# Power_Schematic.net
KiCad netlist of a schematic drawn in Altium Designer
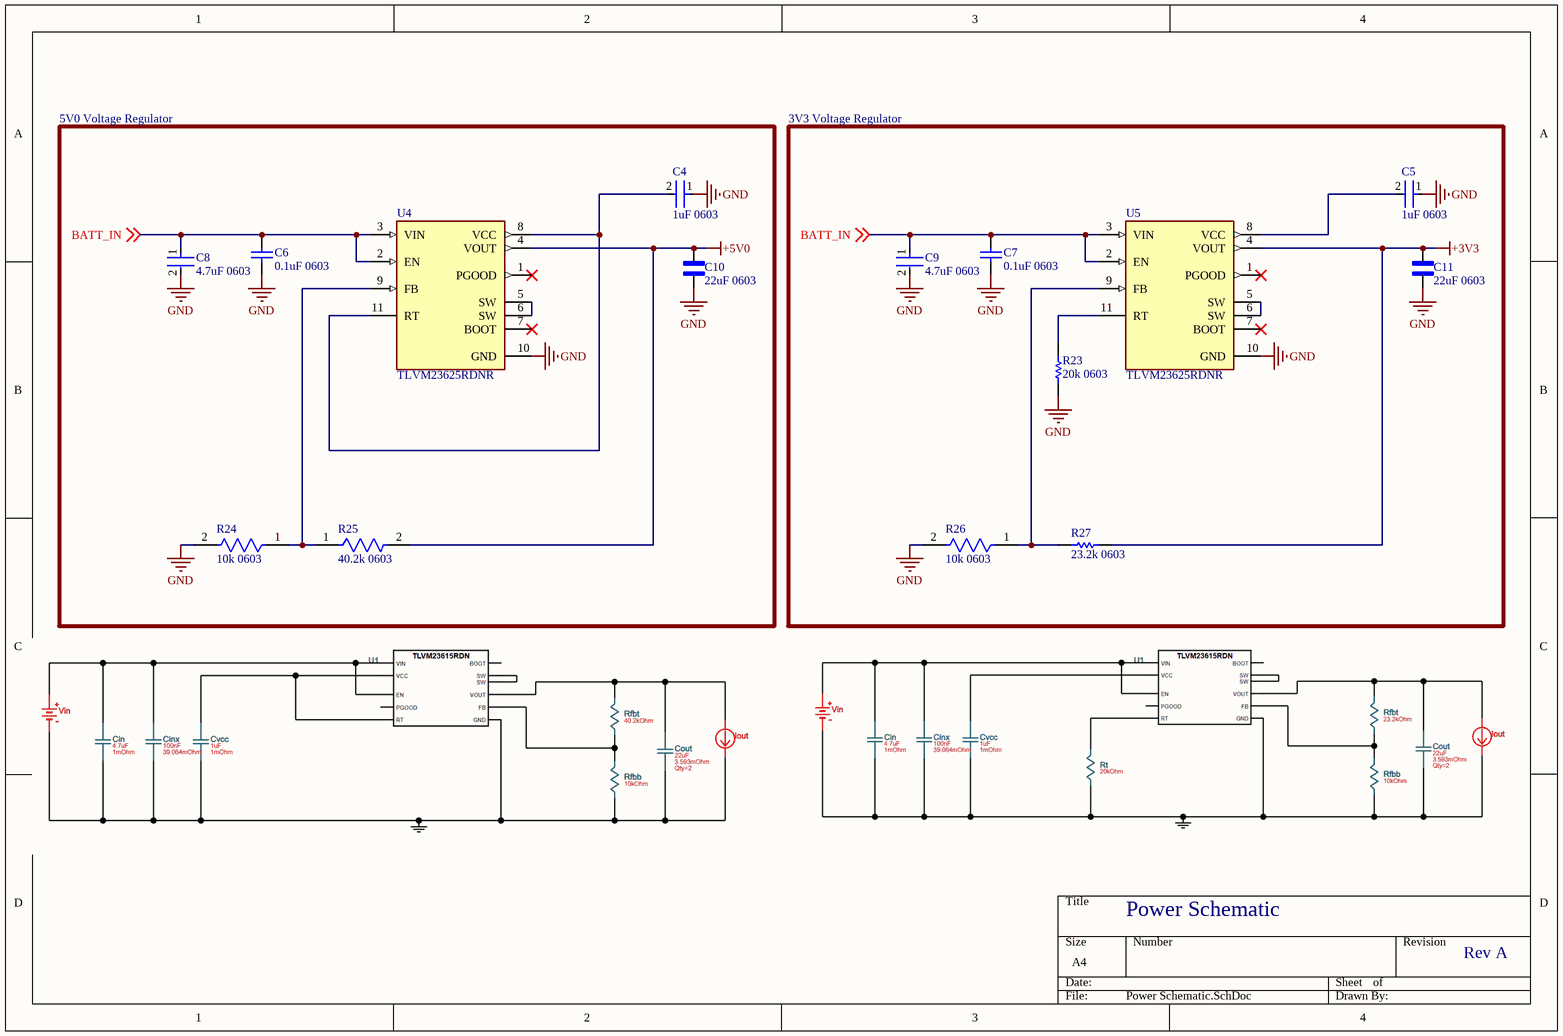
[diagram p0: Power Schematic.SchDoc]

(export (version "E")
  (design (tool "Eeschema 10.0.6"))
  (components
    (comp (ref "C4")
      (value "1uF 0603")
      (footprint "FP-CC0603-DA-MFG")
      (description "CAP CER 1UF 25V X5R 0603")
      (fields
        (field (name "OCTOPART") "https://octopart.com/cc0603krx5r8bb105-yageo-9292811")
        (field (name "MANUFACTURER") "YAGEO")
      )
      (libsource (lib "Altium Content Vault") (part "11868f565c42a9108669ba33697ecf6"))
    )
    (comp (ref "C5")
      (value "1uF 0603")
      (footprint "FP-CC0603-DA-MFG")
      (description "CAP CER 1UF 25V X5R 0603")
      (fields
        (field (name "OCTOPART") "https://octopart.com/cc0603krx5r8bb105-yageo-9292811")
        (field (name "MANUFACTURER") "YAGEO")
      )
      (libsource (lib "Altium Content Vault") (part "11868f565c42a9108669ba33697ecf6"))
    )
    (comp (ref "C6")
      (value "0.1uF 0603")
      (footprint "CAPC1608X90X40LL10T20")
      (fields (field (name "TOLERANCE") "-20%,+80%") (field (name "MANUFACTURER") "Yageo"))
      (libsource (lib "Altium Content Vault") (part "CAP-NP-2"))
    )
    (comp (ref "C7")
      (value "0.1uF 0603")
      (footprint "CAPC1608X90X40LL10T20")
      (fields (field (name "TOLERANCE") "-20%,+80%") (field (name "MANUFACTURER") "Yageo"))
      (libsource (lib "Altium Content Vault") (part "CAP-NP-2"))
    )
    (comp (ref "C8")
      (value "4.7uF 0603")
      (footprint "FP-CC0603-DA-MFG")
      (description "CAP CER 4.7UF 16V X5R 0603")
      (fields
        (field (name "MANUFACTURER") "YAGEO")
        (field (name "MANUFACTURER PART NUMBER") "CC0603KRX5R7BB475")
      )
      (libsource (lib "Altium Content Vault") (part "11868f565c42a9108669ba33697ecf6"))
    )
    (comp (ref "C9")
      (value "4.7uF 0603")
      (footprint "FP-CC0603-DA-MFG")
      (description "CAP CER 4.7UF 16V X5R 0603")
      (fields
        (field (name "MANUFACTURER") "YAGEO")
        (field (name "MANUFACTURER PART NUMBER") "CC0603KRX5R7BB475")
      )
      (libsource (lib "Altium Content Vault") (part "11868f565c42a9108669ba33697ecf6"))
    )
    (comp (ref "C10")
      (value "22uF 0603")
      (footprint "CC0603MRX5R6BB226:CAPC1608X90")
      (description "Cap Ceramic 22uF 10V X5R 20% SMD 0603 85Â°C Paper T/R")
      (fields (field (name "MF") "{'manufacturer': u'Yageo'}") (field (name "MP") "CC0603MRX5R6BB226"))
      (libsource (lib "*") (part "CC0603MRX5R6BB226"))
    )
    (comp (ref "C11")
      (value "22uF 0603")
      (footprint "CC0603MRX5R6BB226:CAPC1608X90")
      (description "Cap Ceramic 22uF 10V X5R 20% SMD 0603 85Â°C Paper T/R")
      (fields (field (name "MF") "{'manufacturer': u'Yageo'}") (field (name "MP") "CC0603MRX5R6BB226"))
      (libsource (lib "*") (part "CC0603MRX5R6BB226"))
    )
    (comp (ref "R23")
      (value "20k 0603")
      (footprint "RESC1608X55X25NL10T15")
      (fields (field (name "PART NUMBER") "RC0603JR-0720RL") (field (name "MANUFACTURER") "Yageo"))
      (libsource (lib "Altium Content Vault") (part "RES"))
    )
    (comp (ref "R24")
      (value "10k 0603")
      (footprint "FP-RC0603-0_55-IPC_C")
      (description "RES 10K OHM 1% 1/10W 0603")
      (fields (field (name "TOLERANCE") "1%"))
      (libsource (lib "Altium Content Vault") (part "1029c3af85768c4190bb7ad29bc67b5"))
    )
    (comp (ref "R25")
      (value "40.2k 0603")
      (footprint "FP-RC0603-0_55-IPC_C")
      (description "RES 40.2K OHM 1% 1/10W 0603")
      (fields (field (name "TOLERANCE") "1%"))
      (libsource (lib "Altium Content Vault") (part "1029c3af85768c4190bb7ad29bc67b5"))
    )
    (comp (ref "R26")
      (value "10k 0603")
      (footprint "FP-RC0603-0_55-IPC_C")
      (description "RES 10K OHM 1% 1/10W 0603")
      (fields (field (name "TOLERANCE") "1%"))
      (libsource (lib "Altium Content Vault") (part "1029c3af85768c4190bb7ad29bc67b5"))
    )
    (comp (ref "R27")
      (value "23.2k 0603")
      (footprint "RESC1608X55X25NL10T15")
      (fields (field (name "PART NUMBER") "RC0603FR-0723K2L") (field (name "MANUFACTURER") "Yageo"))
      (libsource (lib "Altium Content Vault") (part "RES"))
    )
    (comp (ref "U4")
      (value "TLVM23625RDNR")
      (footprint "TLVM23625RDNR:CONV_TLVM23625RDNR")
      (fields (field (name "MF") "{'manufacturer': u'Texas Instruments'}"))
      (libsource (lib "*") (part "TLVM23625RDNR"))
    )
    (comp (ref "U5")
      (value "TLVM23625RDNR")
      (footprint "TLVM23625RDNR:CONV_TLVM23625RDNR")
      (fields (field (name "MF") "{'manufacturer': u'Texas Instruments'}"))
      (libsource (lib "*") (part "TLVM23625RDNR"))
    )
  )
  (nets
    (net (code "1") (name "+3V3") (class "Default")
      (node (ref "C11") (pin "1") (pinfunction "1_1") (pintype "passive"))
      (node (ref "R27") (pin "2") (pinfunction "2_2") (pintype "passive"))
      (node (ref "U5") (pin "4") (pinfunction "VOUT_4") (pintype "output"))
    )
    (net (code "2") (name "+5V0") (class "Default")
      (node (ref "C10") (pin "1") (pinfunction "1_1") (pintype "passive"))
      (node (ref "R25") (pin "2") (pinfunction "2_2") (pintype "passive"))
      (node (ref "U4") (pin "4") (pinfunction "VOUT_4") (pintype "output"))
    )
    (net (code "3") (name "BATT_IN") (class "Default")
      (node (ref "C6") (pin "2") (pinfunction "2_2") (pintype "passive"))
      (node (ref "C7") (pin "2") (pinfunction "2_2") (pintype "passive"))
      (node (ref "C8") (pin "1") (pinfunction "1_1") (pintype "passive"))
      (node (ref "C9") (pin "1") (pinfunction "1_1") (pintype "passive"))
      (node (ref "U4") (pin "2") (pinfunction "EN_2") (pintype "input"))
      (node (ref "U4") (pin "3") (pinfunction "VIN_3") (pintype "input"))
      (node (ref "U5") (pin "2") (pinfunction "EN_2") (pintype "input"))
      (node (ref "U5") (pin "3") (pinfunction "VIN_3") (pintype "input"))
    )
    (net (code "4") (name "GND") (class "Default")
      (node (ref "C10") (pin "2") (pinfunction "2_2") (pintype "passive"))
      (node (ref "C11") (pin "2") (pinfunction "2_2") (pintype "passive"))
      (node (ref "C4") (pin "1") (pinfunction "1_1") (pintype "passive"))
      (node (ref "C5") (pin "1") (pinfunction "1_1") (pintype "passive"))
      (node (ref "C6") (pin "1") (pinfunction "1_1") (pintype "passive"))
      (node (ref "C7") (pin "1") (pinfunction "1_1") (pintype "passive"))
      (node (ref "C8") (pin "2") (pinfunction "2_2") (pintype "passive"))
      (node (ref "C9") (pin "2") (pinfunction "2_2") (pintype "passive"))
      (node (ref "R23") (pin "1") (pinfunction "1_1") (pintype "passive"))
      (node (ref "R24") (pin "2") (pinfunction "2_2") (pintype "passive"))
      (node (ref "R26") (pin "2") (pinfunction "2_2") (pintype "passive"))
      (node (ref "U4") (pin "10") (pinfunction "GND_10") (pintype "power_in"))
      (node (ref "U5") (pin "10") (pinfunction "GND_10") (pintype "power_in"))
    )
    (net (code "5") (name "Net-(U4-FB)") (class "Default")
      (node (ref "R24") (pin "1") (pinfunction "1_1") (pintype "passive"))
      (node (ref "R25") (pin "1") (pinfunction "1_1") (pintype "passive"))
      (node (ref "U4") (pin "9") (pinfunction "FB_9") (pintype "input"))
    )
    (net (code "6") (name "Net-(U4-RT)") (class "Default")
      (node (ref "C4") (pin "2") (pinfunction "2_2") (pintype "passive"))
      (node (ref "U4") (pin "11") (pinfunction "RT_11") (pintype "passive"))
      (node (ref "U4") (pin "8") (pinfunction "VCC_8") (pintype "output"))
    )
    (net (code "7") (name "Net-(U4-SW-Pad5)") (class "Default")
      (node (ref "U4") (pin "5") (pinfunction "SW_5") (pintype "passive"))
      (node (ref "U4") (pin "6") (pinfunction "SW_6") (pintype "passive"))
    )
    (net (code "8") (name "Net-(U5-FB)") (class "Default")
      (node (ref "R26") (pin "1") (pinfunction "1_1") (pintype "passive"))
      (node (ref "R27") (pin "1") (pinfunction "1_1") (pintype "passive"))
      (node (ref "U5") (pin "9") (pinfunction "FB_9") (pintype "input"))
    )
    (net (code "9") (name "Net-(U5-RT)") (class "Default")
      (node (ref "R23") (pin "2") (pinfunction "2_2") (pintype "passive"))
      (node (ref "U5") (pin "11") (pinfunction "RT_11") (pintype "passive"))
    )
    (net (code "10") (name "Net-(U5-SW-Pad5)") (class "Default")
      (node (ref "U5") (pin "5") (pinfunction "SW_5") (pintype "passive"))
      (node (ref "U5") (pin "6") (pinfunction "SW_6") (pintype "passive"))
    )
    (net (code "11") (name "Net-(U5-VCC)") (class "Default")
      (node (ref "C5") (pin "2") (pinfunction "2_2") (pintype "passive"))
      (node (ref "U5") (pin "8") (pinfunction "VCC_8") (pintype "output"))
    )
    (net (code "12") (name "unconnected-(U4-BOOT-Pad7)") (class "Default")
      (node (ref "U4") (pin "7") (pinfunction "BOOT_7") (pintype "passive+no_connect"))
    )
    (net (code "13") (name "unconnected-(U4-PGOOD-Pad1)") (class "Default")
      (node (ref "U4") (pin "1") (pinfunction "PGOOD_1") (pintype "output+no_connect"))
    )
    (net (code "14") (name "unconnected-(U5-BOOT-Pad7)") (class "Default")
      (node (ref "U5") (pin "7") (pinfunction "BOOT_7") (pintype "passive+no_connect"))
    )
    (net (code "15") (name "unconnected-(U5-PGOOD-Pad1)") (class "Default")
      (node (ref "U5") (pin "1") (pinfunction "PGOOD_1") (pintype "output+no_connect"))
    )
  )
)
